# powerboard_3_3V_5V_v1.net
KiCad netlist of a schematic drawn in EAGLE
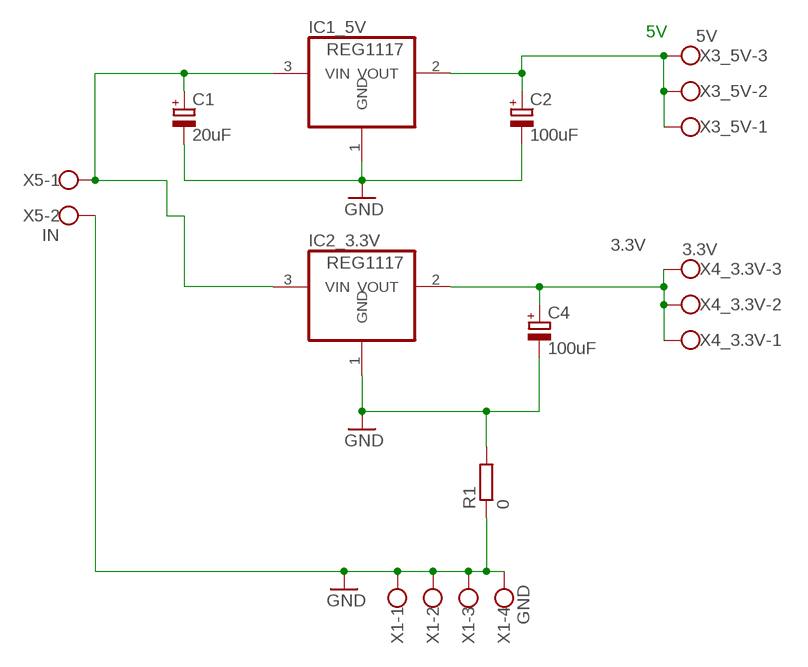
[diagram p0: schematic, sheet 1]

(export (version "E")
  (design (tool "Eeschema 10.0.6"))
  (components
    (comp (ref "C1")
      (value "20uF")
      (footprint "eagle-import:E3,5-8")
      (libsource (lib "eagle-import") (part "CPOL-EUE3.5-8"))
    )
    (comp (ref "C2")
      (value "100uF")
      (footprint "eagle-import:E3,5-8")
      (libsource (lib "eagle-import") (part "CPOL-EUE3.5-8"))
    )
    (comp (ref "C4")
      (value "100uF")
      (footprint "eagle-import:E3,5-8")
      (libsource (lib "eagle-import") (part "CPOL-EUE3.5-8"))
    )
    (comp (ref "IC1_5V")
      (value "REG1117")
      (footprint "eagle-import:SOT223")
      (libsource (lib "eagle-import") (part "REG1117"))
    )
    (comp (ref "IC2_3.3V")
      (value "REG1117")
      (footprint "eagle-import:SOT223")
      (libsource (lib "eagle-import") (part "REG1117"))
    )
    (comp (ref "R1")
      (value "0")
      (footprint "eagle-import:0204_5")
      (libsource (lib "eagle-import") (part "R-EU_0204/5"))
    )
    (comp (ref "X1")
      (value "GND")
      (footprint "eagle-import:W237-4")
      (libsource (lib "eagle-import") (part "W237-4"))
    )
    (comp (ref "X3_5V")
      (value "5V")
      (footprint "eagle-import:W237-103")
      (fields (field (name "MPN") "237-103"))
      (libsource (lib "eagle-import") (part "W237-103"))
    )
    (comp (ref "X4_3.3V")
      (value "3.3V")
      (footprint "eagle-import:W237-103")
      (fields (field (name "MPN") "237-103"))
      (libsource (lib "eagle-import") (part "W237-103"))
    )
    (comp (ref "X5")
      (value "IN")
      (footprint "eagle-import:W237-102")
      (fields (field (name "MPN") "237-102"))
      (libsource (lib "eagle-import") (part "W237-102"))
    )
  )
  (nets
    (net (code "1") (name "/3.3V") (class "Default")
      (node (ref "C4") (pin "+") (pinfunction "+_+") (pintype "passive"))
      (node (ref "IC2_3.3V") (pin "2") (pinfunction "VOUT_2") (pintype "output"))
      (node (ref "X4_3.3V") (pin "1") (pinfunction "KL_1") (pintype "passive"))
      (node (ref "X4_3.3V") (pin "2") (pinfunction "KL_2") (pintype "passive"))
      (node (ref "X4_3.3V") (pin "3") (pinfunction "KL_3") (pintype "passive"))
    )
    (net (code "2") (name "/5V") (class "Default")
      (node (ref "C2") (pin "+") (pinfunction "+_+") (pintype "passive"))
      (node (ref "IC1_5V") (pin "2") (pinfunction "VOUT_2") (pintype "output"))
      (node (ref "X3_5V") (pin "1") (pinfunction "KL_1") (pintype "passive"))
      (node (ref "X3_5V") (pin "2") (pinfunction "KL_2") (pintype "passive"))
      (node (ref "X3_5V") (pin "3") (pinfunction "KL_3") (pintype "passive"))
    )
    (net (code "3") (name "GND") (class "Default")
      (node (ref "C1") (pin "-") (pinfunction "-_-") (pintype "passive"))
      (node (ref "C2") (pin "-") (pinfunction "-_-") (pintype "passive"))
      (node (ref "C4") (pin "-") (pinfunction "-_-") (pintype "passive"))
      (node (ref "IC1_5V") (pin "1") (pinfunction "GND_1") (pintype "power_in"))
      (node (ref "IC2_3.3V") (pin "1") (pinfunction "GND_1") (pintype "power_in"))
      (node (ref "R1") (pin "1") (pinfunction "1_1") (pintype "passive"))
      (node (ref "R1") (pin "2") (pinfunction "2_2") (pintype "passive"))
      (node (ref "X1") (pin "1") (pinfunction "KL_1") (pintype "passive"))
      (node (ref "X1") (pin "2") (pinfunction "KL_2") (pintype "passive"))
      (node (ref "X1") (pin "3") (pinfunction "KL_3") (pintype "passive"))
      (node (ref "X1") (pin "4") (pinfunction "KL_4") (pintype "passive"))
      (node (ref "X5") (pin "2") (pinfunction "KL_2") (pintype "passive"))
    )
    (net (code "4") (name "Net-(IC1_5V-VIN)") (class "Default")
      (node (ref "C1") (pin "+") (pinfunction "+_+") (pintype "passive"))
      (node (ref "IC1_5V") (pin "3") (pinfunction "VIN_3") (pintype "input"))
      (node (ref "IC2_3.3V") (pin "3") (pinfunction "VIN_3") (pintype "input"))
      (node (ref "X5") (pin "1") (pinfunction "KL_1") (pintype "passive"))
    )
  )
)
